# hunger_cube.net
KiCad netlist of a schematic drawn in EAGLE
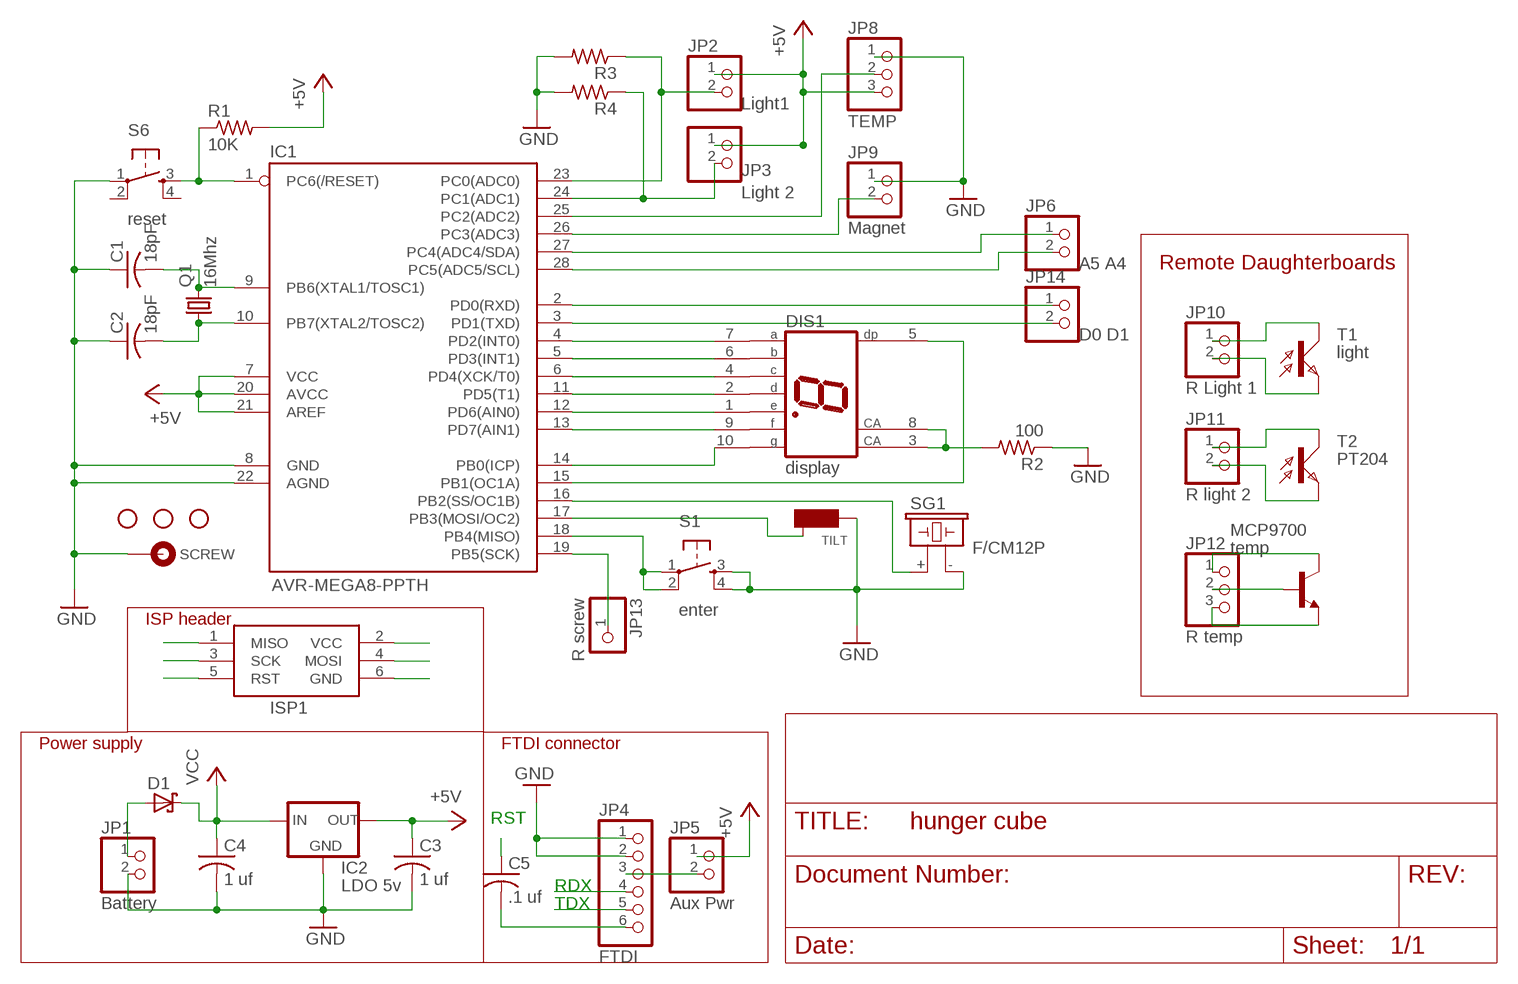
[diagram p0: schematic, sheet 1]

(export (version "E")
  (design (tool "Eeschema 10.0.6"))
  (components
    (comp (ref "C1")
      (value "18pF")
      (footprint "eagle-import:C025-050X050")
      (libsource (lib "eagle-import") (part "C-US025-050X050"))
    )
    (comp (ref "C2")
      (value "18pF")
      (footprint "eagle-import:C025-050X050")
      (libsource (lib "eagle-import") (part "C-US025-050X050"))
    )
    (comp (ref "C3")
      (value "1 uf")
      (footprint "eagle-import:C025-050X050")
      (libsource (lib "eagle-import") (part "C-US025-050X050"))
    )
    (comp (ref "C4")
      (value "1 uf")
      (footprint "eagle-import:C025-050X050")
      (libsource (lib "eagle-import") (part "C-US025-050X050"))
    )
    (comp (ref "C5")
      (value ".1 uf")
      (footprint "eagle-import:C025-050X050")
      (libsource (lib "eagle-import") (part "C-US025-050X050"))
    )
    (comp (ref "D1")
      (value "SCHOTTKY-DIODEDO41")
      (footprint "eagle-import:DO41-10")
      (libsource (lib "eagle-import") (part "SCHOTTKY-DIODEDO41"))
    )
    (comp (ref "DIS1")
      (value "display")
      (footprint "eagle-import:HDSP-M")
      (libsource (lib "eagle-import") (part "HD-H101"))
    )
    (comp (ref "IC1")
      (value "AVR-MEGA8-PPTH")
      (footprint "eagle-import:DIL28-3")
      (libsource (lib "eagle-import") (part "AVR-MEGA8-PPTH"))
    )
    (comp (ref "IC2")
      (value "LDO 5v")
      (footprint "eagle-import:TO92-INLINE")
      (libsource (lib "eagle-import") (part "MCP1700INLINE"))
    )
    (comp (ref "ISP1")
      (value "AVRISP-6")
      (footprint "eagle-import:AVRISP")
      (libsource (lib "eagle-import") (part "AVRISP-6"))
    )
    (comp (ref "JP1")
      (value "Battery")
      (footprint "eagle-import:1X02")
      (libsource (lib "eagle-import") (part "PINHD-1X2"))
    )
    (comp (ref "JP2")
      (value "Light1")
      (footprint "eagle-import:1X02")
      (libsource (lib "eagle-import") (part "PINHD-1X2"))
    )
    (comp (ref "JP3")
      (value "Light 2")
      (footprint "eagle-import:1X02")
      (libsource (lib "eagle-import") (part "PINHD-1X2"))
    )
    (comp (ref "JP4")
      (value "FTDI")
      (footprint "eagle-import:1X06")
      (libsource (lib "eagle-import") (part "PINHD-1X6"))
    )
    (comp (ref "JP5")
      (value "Aux Pwr")
      (footprint "eagle-import:1X02")
      (libsource (lib "eagle-import") (part "PINHD-1X2"))
    )
    (comp (ref "JP6")
      (value "A5 A4")
      (footprint "eagle-import:1X02")
      (libsource (lib "eagle-import") (part "PINHD-1X2"))
    )
    (comp (ref "JP7")
      (value "Connected screw hole")
      (footprint "eagle-import:SCREW-HOLE-PAD")
      (libsource (lib "eagle-import") (part "CONNECTED-SCREW-HOLE"))
    )
    (comp (ref "JP8")
      (value "TEMP")
      (footprint "eagle-import:1X03")
      (libsource (lib "eagle-import") (part "PINHD-1X3"))
    )
    (comp (ref "JP9")
      (value "Magnet")
      (footprint "eagle-import:1X02")
      (libsource (lib "eagle-import") (part "PINHD-1X2"))
    )
    (comp (ref "JP10")
      (value "R Light 1")
      (footprint "eagle-import:1X02")
      (libsource (lib "eagle-import") (part "PINHD-1X2"))
    )
    (comp (ref "JP11")
      (value "R light 2")
      (footprint "eagle-import:1X02")
      (libsource (lib "eagle-import") (part "PINHD-1X2"))
    )
    (comp (ref "JP12")
      (value "R temp")
      (footprint "eagle-import:1X03")
      (libsource (lib "eagle-import") (part "PINHD-1X3"))
    )
    (comp (ref "JP13")
      (value "R screw")
      (footprint "eagle-import:1X01")
      (libsource (lib "eagle-import") (part "PINHD-1X1"))
    )
    (comp (ref "JP14")
      (value "D0 D1")
      (footprint "eagle-import:1X02")
      (libsource (lib "eagle-import") (part "PINHD-1X2"))
    )
    (comp (ref "MCP9700")
      (value "temp")
      (footprint "eagle-import:TO92-EBC")
      (libsource (lib "eagle-import") (part "-NPN-TO92-EBC"))
    )
    (comp (ref "Q1")
      (value "16Mhz")
      (footprint "eagle-import:HC49US")
      (libsource (lib "eagle-import") (part "CRYSTALHC49US"))
    )
    (comp (ref "R1")
      (value "10K")
      (footprint "eagle-import:0207_12")
      (libsource (lib "eagle-import") (part "R-US_0207/12"))
    )
    (comp (ref "R2")
      (value "100")
      (footprint "eagle-import:0207_12")
      (libsource (lib "eagle-import") (part "R-US_0207/12"))
    )
    (comp (ref "R3")
      (value "R-US_0207/12")
      (footprint "eagle-import:0207_12")
      (libsource (lib "eagle-import") (part "R-US_0207/12"))
    )
    (comp (ref "R4")
      (value "R-US_0207/12")
      (footprint "eagle-import:0207_12")
      (libsource (lib "eagle-import") (part "R-US_0207/12"))
    )
    (comp (ref "S1")
      (value "enter")
      (footprint "eagle-import:TACTILE-PTH")
      (libsource (lib "eagle-import") (part "TAC_SWITCHPTH"))
    )
    (comp (ref "S6")
      (value "reset")
      (footprint "eagle-import:TACTILE-PTH")
      (libsource (lib "eagle-import") (part "TAC_SWITCHPTH"))
    )
    (comp (ref "SG1")
      (value "F/CM12P")
      (footprint "eagle-import:F_CM12P")
      (libsource (lib "eagle-import") (part "F/CM12P"))
    )
    (comp (ref "ST1")
      (value "STAND-OFF")
      (footprint "eagle-import:STAND-OFF")
      (libsource (lib "eagle-import") (part "STAND-OFF"))
    )
    (comp (ref "ST2")
      (value "STAND-OFF")
      (footprint "eagle-import:STAND-OFF")
      (libsource (lib "eagle-import") (part "STAND-OFF"))
    )
    (comp (ref "ST3")
      (value "STAND-OFF")
      (footprint "eagle-import:STAND-OFF")
      (libsource (lib "eagle-import") (part "STAND-OFF"))
    )
    (comp (ref "T1")
      (value "light")
      (footprint "eagle-import:BPX81")
      (libsource (lib "eagle-import") (part "BPX81"))
    )
    (comp (ref "T2")
      (value "PT204")
      (footprint "eagle-import:BPX81")
      (libsource (lib "eagle-import") (part "BPX81"))
    )
    (comp (ref "TILT")
      (value "TILT-SENSOR")
      (footprint "eagle-import:TILT")
      (libsource (lib "eagle-import") (part "TILT-SENSOR"))
    )
  )
  (nets
    (net (code "1") (name "+5V") (class "Default")
      (node (ref "C3") (pin "1") (pinfunction "1_1") (pintype "passive"))
      (node (ref "IC1") (pin "20") (pinfunction "AVCC_20") (pintype "bidirectional"))
      (node (ref "IC1") (pin "21") (pinfunction "AREF_21") (pintype "bidirectional"))
      (node (ref "IC1") (pin "7") (pinfunction "VCC_7") (pintype "bidirectional"))
      (node (ref "IC2") (pin "3") (pinfunction "OUT_3") (pintype "passive"))
      (node (ref "ISP1") (pin "2") (pinfunction "VCC_2") (pintype "power_in"))
      (node (ref "JP2") (pin "1") (pinfunction "1_1") (pintype "passive"))
      (node (ref "JP3") (pin "1") (pinfunction "1_1") (pintype "passive"))
      (node (ref "JP5") (pin "1") (pinfunction "1_1") (pintype "passive"))
      (node (ref "JP8") (pin "3") (pinfunction "3_3") (pintype "passive"))
      (node (ref "R1") (pin "2") (pinfunction "2_2") (pintype "passive"))
    )
    (net (code "2") (name "/D0-RDX") (class "Default")
      (node (ref "IC1") (pin "2") (pinfunction "PD0(RXD)_2") (pintype "bidirectional"))
      (node (ref "JP14") (pin "1") (pinfunction "1_1") (pintype "passive"))
      (node (ref "JP4") (pin "4") (pinfunction "4_4") (pintype "passive"))
    )
    (net (code "3") (name "/D1-TDX") (class "Default")
      (node (ref "IC1") (pin "3") (pinfunction "PD1(TXD)_3") (pintype "bidirectional"))
      (node (ref "JP14") (pin "2") (pinfunction "2_2") (pintype "passive"))
      (node (ref "JP4") (pin "5") (pinfunction "5_5") (pintype "passive"))
    )
    (net (code "4") (name "/D11-MOSI-TILT") (class "Default")
      (node (ref "IC1") (pin "17") (pinfunction "PB3(MOSI/OC2)_17") (pintype "bidirectional"))
      (node (ref "ISP1") (pin "4") (pinfunction "MOSI_4") (pintype "output"))
      (node (ref "TILT") (pin "SLEEVE") (pinfunction "SLEEVE_SLEEVE") (pintype "bidirectional"))
    )
    (net (code "5") (name "/D12-MISO-ENTER") (class "Default")
      (node (ref "IC1") (pin "18") (pinfunction "PB4(MISO)_18") (pintype "bidirectional"))
      (node (ref "ISP1") (pin "1") (pinfunction "MISO_1") (pintype "input"))
      (node (ref "S1") (pin "1") (pinfunction "1_1") (pintype "passive"))
      (node (ref "S1") (pin "2") (pinfunction "2_2") (pintype "passive"))
    )
    (net (code "6") (name "/D13-SCK-SCREW") (class "Default")
      (node (ref "IC1") (pin "19") (pinfunction "PB5(SCK)_19") (pintype "bidirectional"))
      (node (ref "ISP1") (pin "3") (pinfunction "SCK_3") (pintype "output"))
      (node (ref "JP13") (pin "1") (pinfunction "1_1") (pintype "passive"))
    )
    (net (code "7") (name "/RST") (class "Default")
      (node (ref "C5") (pin "1") (pinfunction "1_1") (pintype "passive"))
      (node (ref "IC1") (pin "1") (pinfunction "PC6(/RESET)_1") (pintype "bidirectional"))
      (node (ref "ISP1") (pin "5") (pinfunction "RST_5") (pintype "output"))
      (node (ref "R1") (pin "1") (pinfunction "1_1") (pintype "passive"))
      (node (ref "S6") (pin "3") (pinfunction "3_3") (pintype "passive"))
    )
    (net (code "8") (name "GND") (class "Default")
      (node (ref "C1") (pin "1") (pinfunction "1_1") (pintype "passive"))
      (node (ref "C2") (pin "1") (pinfunction "1_1") (pintype "passive"))
      (node (ref "C3") (pin "2") (pinfunction "2_2") (pintype "passive"))
      (node (ref "C4") (pin "2") (pinfunction "2_2") (pintype "passive"))
      (node (ref "IC1") (pin "22") (pinfunction "AGND_22") (pintype "bidirectional"))
      (node (ref "IC1") (pin "8") (pinfunction "GND_8") (pintype "bidirectional"))
      (node (ref "IC2") (pin "1") (pinfunction "GND_1") (pintype "input"))
      (node (ref "ISP1") (pin "6") (pinfunction "GND_6") (pintype "power_in"))
      (node (ref "JP1") (pin "2") (pinfunction "2_2") (pintype "passive"))
      (node (ref "JP4") (pin "1") (pinfunction "1_1") (pintype "passive"))
      (node (ref "JP4") (pin "2") (pinfunction "2_2") (pintype "passive"))
      (node (ref "JP7") (pin "SCREW") (pinfunction "SCREW_SCREW") (pintype "bidirectional"))
      (node (ref "JP8") (pin "1") (pinfunction "1_1") (pintype "passive"))
      (node (ref "JP9") (pin "1") (pinfunction "1_1") (pintype "passive"))
      (node (ref "R2") (pin "1") (pinfunction "1_1") (pintype "passive"))
      (node (ref "R3") (pin "2") (pinfunction "2_2") (pintype "passive"))
      (node (ref "R4") (pin "2") (pinfunction "2_2") (pintype "passive"))
      (node (ref "S1") (pin "3") (pinfunction "3_3") (pintype "passive"))
      (node (ref "S1") (pin "4") (pinfunction "4_4") (pintype "passive"))
      (node (ref "S6") (pin "1") (pinfunction "1_1") (pintype "passive"))
      (node (ref "SG1") (pin "-") (pinfunction "2_-") (pintype "passive"))
      (node (ref "TILT") (pin "CENTER") (pinfunction "CENTER_CENTER") (pintype "bidirectional"))
    )
    (net (code "9") (name "Net-(C5-Pad2)") (class "Default")
      (node (ref "C5") (pin "2") (pinfunction "2_2") (pintype "passive"))
      (node (ref "JP4") (pin "6") (pinfunction "6_6") (pintype "passive"))
    )
    (net (code "10") (name "Net-(D1-PadA)") (class "Default")
      (node (ref "D1") (pin "A") (pinfunction "A_A") (pintype "passive"))
      (node (ref "JP1") (pin "1") (pinfunction "1_1") (pintype "passive"))
    )
    (net (code "11") (name "Net-(DIS1-A)") (class "Default")
      (node (ref "DIS1") (pin "7") (pinfunction "A_7") (pintype "passive"))
      (node (ref "IC1") (pin "4") (pinfunction "PD2(INT0)_4") (pintype "bidirectional"))
    )
    (net (code "12") (name "Net-(DIS1-B)") (class "Default")
      (node (ref "DIS1") (pin "6") (pinfunction "B_6") (pintype "passive"))
      (node (ref "IC1") (pin "5") (pinfunction "PD3(INT1)_5") (pintype "bidirectional"))
    )
    (net (code "13") (name "Net-(DIS1-C)") (class "Default")
      (node (ref "DIS1") (pin "4") (pinfunction "C_4") (pintype "passive"))
      (node (ref "IC1") (pin "6") (pinfunction "PD4(XCK/T0)_6") (pintype "bidirectional"))
    )
    (net (code "14") (name "Net-(DIS1-CA-Pad3)") (class "Default")
      (node (ref "DIS1") (pin "3") (pinfunction "CA_3") (pintype "passive"))
      (node (ref "DIS1") (pin "8") (pinfunction "CA_8") (pintype "passive"))
      (node (ref "R2") (pin "2") (pinfunction "2_2") (pintype "passive"))
    )
    (net (code "15") (name "Net-(DIS1-D)") (class "Default")
      (node (ref "DIS1") (pin "2") (pinfunction "D_2") (pintype "passive"))
      (node (ref "IC1") (pin "11") (pinfunction "PD5(T1)_11") (pintype "bidirectional"))
    )
    (net (code "16") (name "Net-(DIS1-DP)") (class "Default")
      (node (ref "DIS1") (pin "5") (pinfunction "DP_5") (pintype "passive"))
      (node (ref "IC1") (pin "15") (pinfunction "PB1(OC1A)_15") (pintype "bidirectional"))
    )
    (net (code "17") (name "Net-(DIS1-E)") (class "Default")
      (node (ref "DIS1") (pin "1") (pinfunction "E_1") (pintype "passive"))
      (node (ref "IC1") (pin "12") (pinfunction "PD6(AIN0)_12") (pintype "bidirectional"))
    )
    (net (code "18") (name "Net-(DIS1-F)") (class "Default")
      (node (ref "DIS1") (pin "9") (pinfunction "F_9") (pintype "passive"))
      (node (ref "IC1") (pin "13") (pinfunction "PD7(AIN1)_13") (pintype "bidirectional"))
    )
    (net (code "19") (name "Net-(DIS1-G)") (class "Default")
      (node (ref "DIS1") (pin "10") (pinfunction "G_10") (pintype "passive"))
      (node (ref "IC1") (pin "14") (pinfunction "PB0(ICP)_14") (pintype "bidirectional"))
    )
    (net (code "20") (name "Net-(IC1-PB2(SS{slash}OC1B))") (class "Default")
      (node (ref "IC1") (pin "16") (pinfunction "PB2(SS/OC1B)_16") (pintype "bidirectional"))
      (node (ref "SG1") (pin "+") (pinfunction "1_+") (pintype "passive"))
    )
    (net (code "21") (name "Net-(IC1-PB6(XTAL1{slash}TOSC1))") (class "Default")
      (node (ref "C1") (pin "2") (pinfunction "2_2") (pintype "passive"))
      (node (ref "IC1") (pin "9") (pinfunction "PB6(XTAL1/TOSC1)_9") (pintype "bidirectional"))
      (node (ref "Q1") (pin "2") (pinfunction "2_2") (pintype "passive"))
    )
    (net (code "22") (name "Net-(IC1-PB7(XTAL2{slash}TOSC2))") (class "Default")
      (node (ref "C2") (pin "2") (pinfunction "2_2") (pintype "passive"))
      (node (ref "IC1") (pin "10") (pinfunction "PB7(XTAL2/TOSC2)_10") (pintype "bidirectional"))
      (node (ref "Q1") (pin "1") (pinfunction "1_1") (pintype "passive"))
    )
    (net (code "23") (name "Net-(IC1-PC0(ADC0))") (class "Default")
      (node (ref "IC1") (pin "23") (pinfunction "PC0(ADC0)_23") (pintype "bidirectional"))
      (node (ref "JP2") (pin "2") (pinfunction "2_2") (pintype "passive"))
      (node (ref "R3") (pin "1") (pinfunction "1_1") (pintype "passive"))
    )
    (net (code "24") (name "Net-(IC1-PC1(ADC1))") (class "Default")
      (node (ref "IC1") (pin "24") (pinfunction "PC1(ADC1)_24") (pintype "bidirectional"))
      (node (ref "JP3") (pin "2") (pinfunction "2_2") (pintype "passive"))
      (node (ref "R4") (pin "1") (pinfunction "1_1") (pintype "passive"))
    )
    (net (code "25") (name "Net-(IC1-PC2(ADC2))") (class "Default")
      (node (ref "IC1") (pin "25") (pinfunction "PC2(ADC2)_25") (pintype "bidirectional"))
      (node (ref "JP8") (pin "2") (pinfunction "2_2") (pintype "passive"))
    )
    (net (code "26") (name "Net-(IC1-PC3(ADC3))") (class "Default")
      (node (ref "IC1") (pin "26") (pinfunction "PC3(ADC3)_26") (pintype "bidirectional"))
      (node (ref "JP9") (pin "2") (pinfunction "2_2") (pintype "passive"))
    )
    (net (code "27") (name "Net-(IC1-PC4(ADC4{slash}SDA))") (class "Default")
      (node (ref "IC1") (pin "27") (pinfunction "PC4(ADC4/SDA)_27") (pintype "bidirectional"))
      (node (ref "JP6") (pin "1") (pinfunction "1_1") (pintype "passive"))
    )
    (net (code "28") (name "Net-(IC1-PC5(ADC5{slash}SCL))") (class "Default")
      (node (ref "IC1") (pin "28") (pinfunction "PC5(ADC5/SCL)_28") (pintype "bidirectional"))
      (node (ref "JP6") (pin "2") (pinfunction "2_2") (pintype "passive"))
    )
    (net (code "29") (name "Net-(JP4-Pad3)") (class "Default")
      (node (ref "JP4") (pin "3") (pinfunction "3_3") (pintype "passive"))
      (node (ref "JP5") (pin "2") (pinfunction "2_2") (pintype "passive"))
    )
    (net (code "30") (name "Net-(JP10-Pad1)") (class "Default")
      (node (ref "JP10") (pin "1") (pinfunction "1_1") (pintype "passive"))
      (node (ref "T1") (pin "C") (pinfunction "C_C") (pintype "passive"))
    )
    (net (code "31") (name "Net-(JP10-Pad2)") (class "Default")
      (node (ref "JP10") (pin "2") (pinfunction "2_2") (pintype "passive"))
      (node (ref "T1") (pin "E") (pinfunction "E_E") (pintype "passive"))
    )
    (net (code "32") (name "Net-(JP11-Pad1)") (class "Default")
      (node (ref "JP11") (pin "1") (pinfunction "1_1") (pintype "passive"))
      (node (ref "T2") (pin "C") (pinfunction "C_C") (pintype "passive"))
    )
    (net (code "33") (name "Net-(JP11-Pad2)") (class "Default")
      (node (ref "JP11") (pin "2") (pinfunction "2_2") (pintype "passive"))
      (node (ref "T2") (pin "E") (pinfunction "E_E") (pintype "passive"))
    )
    (net (code "34") (name "Net-(JP12-Pad1)") (class "Default")
      (node (ref "JP12") (pin "1") (pinfunction "1_1") (pintype "passive"))
      (node (ref "MCP9700") (pin "C") (pinfunction "C_C") (pintype "passive"))
    )
    (net (code "35") (name "Net-(JP12-Pad2)") (class "Default")
      (node (ref "JP12") (pin "2") (pinfunction "2_2") (pintype "passive"))
      (node (ref "MCP9700") (pin "B") (pinfunction "B_B") (pintype "passive"))
    )
    (net (code "36") (name "Net-(JP12-Pad3)") (class "Default")
      (node (ref "JP12") (pin "3") (pinfunction "3_3") (pintype "passive"))
      (node (ref "MCP9700") (pin "E") (pinfunction "E_E") (pintype "passive"))
    )
    (net (code "37") (name "VCC") (class "Default")
      (node (ref "C4") (pin "1") (pinfunction "1_1") (pintype "passive"))
      (node (ref "D1") (pin "C") (pinfunction "C_C") (pintype "passive"))
      (node (ref "IC2") (pin "2") (pinfunction "IN_2") (pintype "input"))
    )
    (net (code "38") (name "unconnected-(S6-Pad2)") (class "Default")
      (node (ref "S6") (pin "2") (pinfunction "2_2") (pintype "passive"))
    )
    (net (code "39") (name "unconnected-(S6-Pad4)") (class "Default")
      (node (ref "S6") (pin "4") (pinfunction "4_4") (pintype "passive"))
    )
  )
)
